# synth-zodiac-aquarius-vco.net
KiCad netlist of a schematic drawn in EAGLE
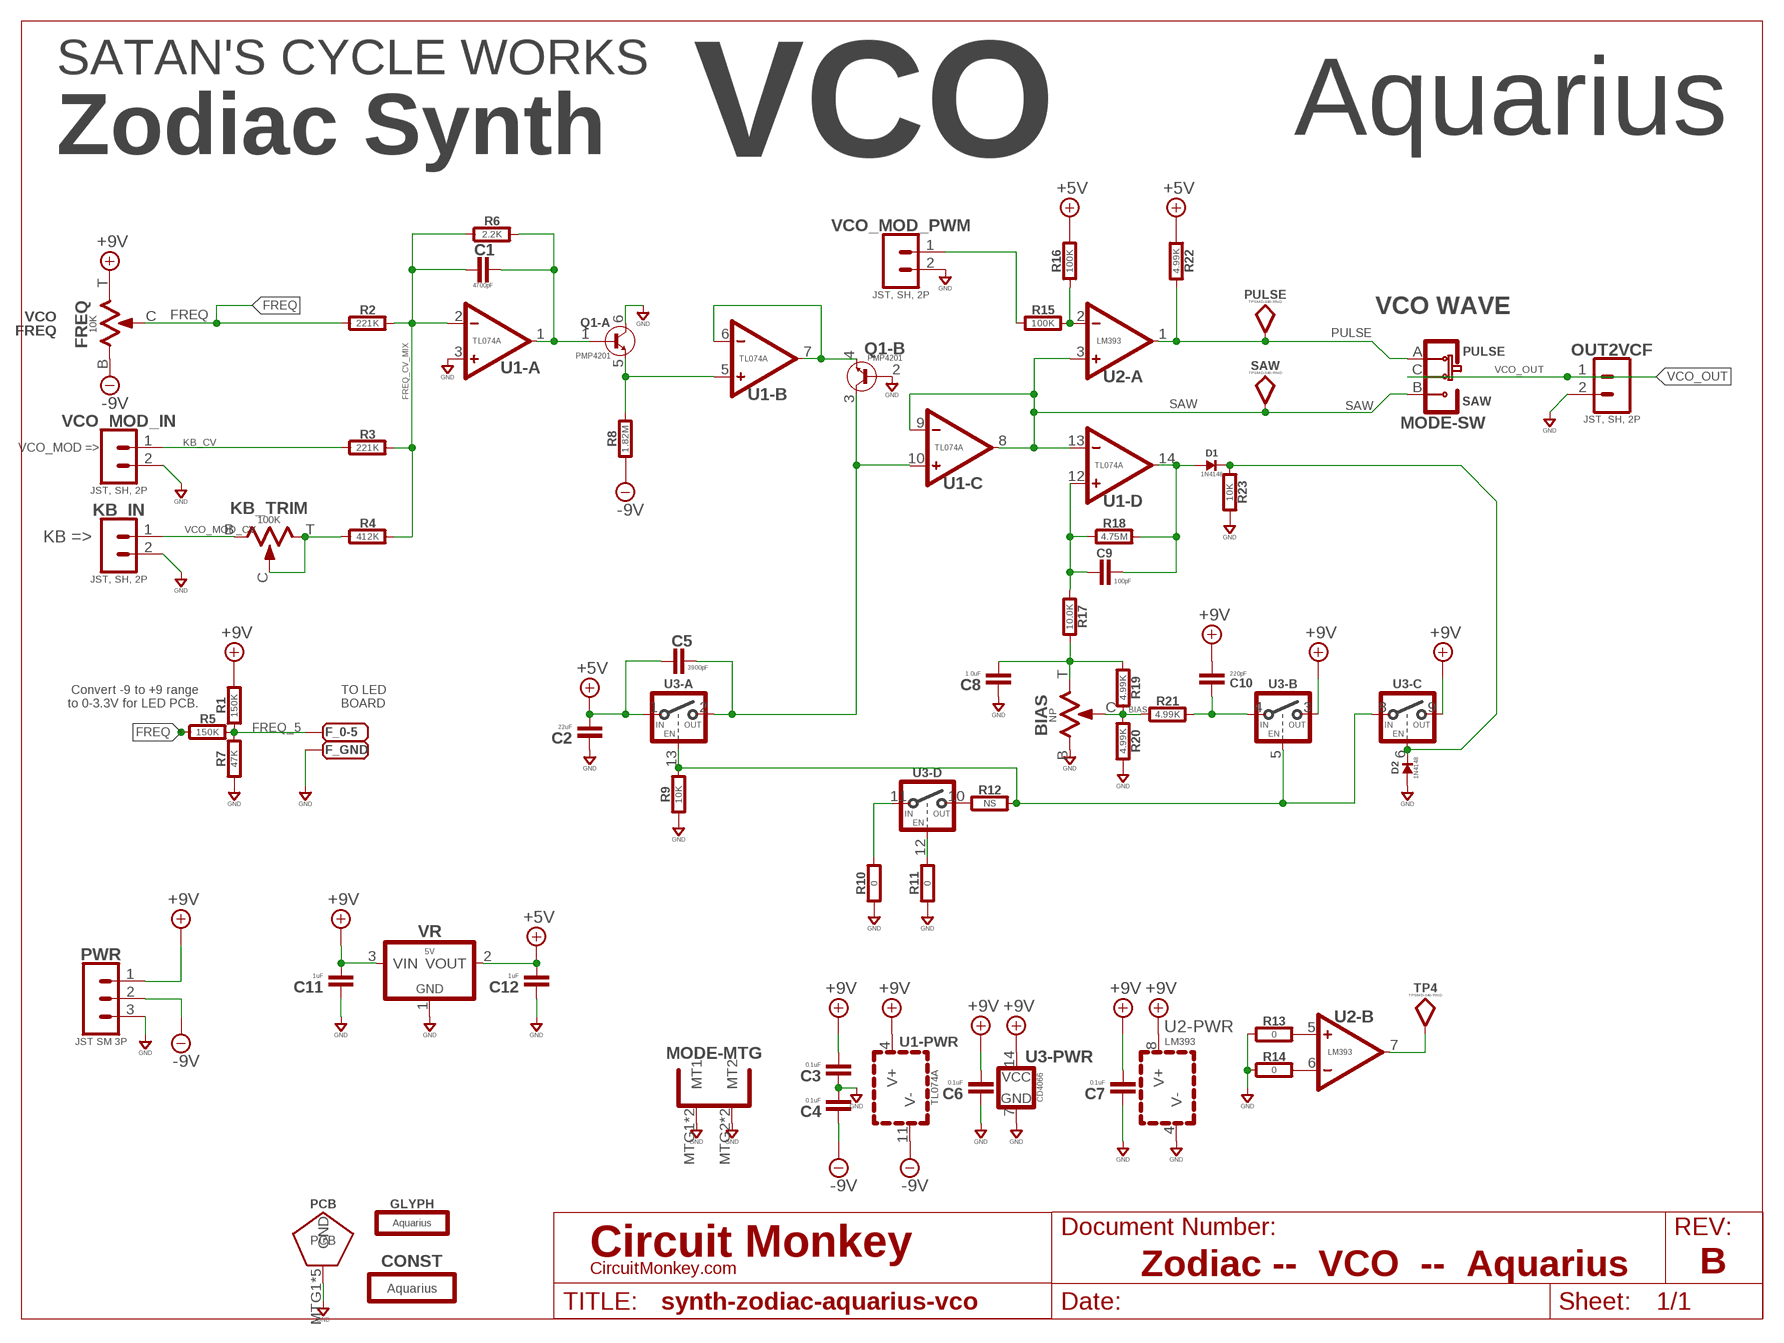
[diagram p0: schematic, sheet 1]

(export (version "E")
  (design (tool "Eeschema 10.0.6"))
  (components
    (comp (ref "BIAS")
      (value "NP")
      (footprint "eagle-import:TRIM_BOURNS_TC33X")
      (fields (field (name "MFR") "Bourns") (field (name "MPN") "TC33X"))
      (libsource (lib "eagle-import") (part "TRIMPOTTC33X"))
    )
    (comp (ref "C1")
      (value "4700pF")
      (footprint "eagle-import:0603-CAP")
      (libsource (lib "eagle-import") (part "CAPACITOR0603"))
    )
    (comp (ref "C2")
      (value "22uF")
      (footprint "eagle-import:0603-CAP")
      (libsource (lib "eagle-import") (part "CAPACITOR0603"))
    )
    (comp (ref "C3")
      (value "0.1uF")
      (footprint "eagle-import:0603-CAP")
      (libsource (lib "eagle-import") (part "CAPACITOR0603"))
    )
    (comp (ref "C4")
      (value "0.1uF")
      (footprint "eagle-import:0603-CAP")
      (libsource (lib "eagle-import") (part "CAPACITOR0603"))
    )
    (comp (ref "C5")
      (value "3900pF")
      (footprint "eagle-import:0603-CAP")
      (libsource (lib "eagle-import") (part "CAPACITOR0603"))
    )
    (comp (ref "C6")
      (value "0.1uF")
      (footprint "eagle-import:0603-CAP")
      (libsource (lib "eagle-import") (part "CAPACITOR0603"))
    )
    (comp (ref "C7")
      (value "0.1uF")
      (footprint "eagle-import:0603-CAP")
      (libsource (lib "eagle-import") (part "CAPACITOR0603"))
    )
    (comp (ref "C8")
      (value "1.0uF")
      (footprint "eagle-import:0603-CAP")
      (libsource (lib "eagle-import") (part "CAPACITOR0603"))
    )
    (comp (ref "C9")
      (value "100pF")
      (footprint "eagle-import:0603-CAP")
      (libsource (lib "eagle-import") (part "CAPACITOR0603"))
    )
    (comp (ref "C10")
      (value "220pF")
      (footprint "eagle-import:0603-CAP")
      (libsource (lib "eagle-import") (part "CAPACITOR0603"))
    )
    (comp (ref "C11")
      (value "1uF")
      (footprint "eagle-import:0603-CAP")
      (libsource (lib "eagle-import") (part "CAPACITOR0603"))
    )
    (comp (ref "C12")
      (value "1uF")
      (footprint "eagle-import:0603-CAP")
      (libsource (lib "eagle-import") (part "CAPACITOR0603"))
    )
    (comp (ref "CONST")
      (value "Aquarius")
      (footprint "eagle-import:AQUARIUS-CONST")
      (libsource (lib "eagle-import") (part "CONSTELLATION-AQUARIUS"))
    )
    (comp (ref "D1")
      (value "1N4148")
      (footprint "eagle-import:SOD-123")
      (fields (field (name "MPN") "1N4148W"))
      (libsource (lib "eagle-import") (part "DIODE-1N4148"))
    )
    (comp (ref "D2")
      (value "1N4148")
      (footprint "eagle-import:SOD-123")
      (fields (field (name "MPN") "1N4148W"))
      (libsource (lib "eagle-import") (part "DIODE-1N4148"))
    )
    (comp (ref "FREQ")
      (value "10K")
      (footprint "eagle-import:POT-RV9110")
      (fields (field (name "MFR") "Tayda") (field (name "MPN") "RV9110NO-OS15A00"))
      (libsource (lib "eagle-import") (part "TRIMPOT9MM_PCB_SHAFT"))
    )
    (comp (ref "F_0-5")
      (value "PADSMD-070X070")
      (footprint "eagle-import:SMD-070MIL")
      (libsource (lib "eagle-import") (part "PADSMD-070X070"))
    )
    (comp (ref "F_GND")
      (value "PADSMD-070X070")
      (footprint "eagle-import:SMD-070MIL")
      (libsource (lib "eagle-import") (part "PADSMD-070X070"))
    )
    (comp (ref "GLYPH")
      (value "Aquarius")
      (footprint "eagle-import:AQUARIUS-GLYPH")
      (libsource (lib "eagle-import") (part "GLYPH-AQUARIUS"))
    )
    (comp (ref "KB_IN")
      (value "JST, SH, 2P")
      (footprint "eagle-import:BM02B-SRSS-TB")
      (fields (field (name "MFR") "JST") (field (name "MPN") "BMB02B-SRSS-TB"))
      (libsource (lib "eagle-import") (part "02P-SM-VT-SMT"))
    )
    (comp (ref "KB_TRIM")
      (value "100K")
      (footprint "eagle-import:TRIM_BOURNS_TC33X")
      (fields (field (name "MFR") "Bourns") (field (name "MPN") "TC33X"))
      (libsource (lib "eagle-import") (part "TRIMPOTTC33X"))
    )
    (comp (ref "MODE")
      (value "SLIDE-SPDT-MNTSS-12-F45-TH-PCB-2")
      (footprint "eagle-import:SS-12-F45-PNL-SMT-2")
      (fields (field (name "MFR") "Tayda") (field (name "MPN") "A-659/A-5111/A-5104"))
      (libsource (lib "eagle-import") (part "SLIDE-SPDT-MNTSS-12-F45-TH-PCB-2"))
    )
    (comp (ref "OUT2VCF")
      (value "JST, SH, 2P")
      (footprint "eagle-import:BM02B-SRSS-TB")
      (fields (field (name "MFR") "JST") (field (name "MPN") "BMB02B-SRSS-TB"))
      (libsource (lib "eagle-import") (part "02P-SM-VT-SMT"))
    )
    (comp (ref "PCB")
      (value "PCB FAB")
      (footprint "eagle-import:PENTAGON-40MM-RAD")
      (libsource (lib "eagle-import") (part "PENTAGON-40R"))
    )
    (comp (ref "PULSE")
      (value "TPSMD-040-RND")
      (footprint "eagle-import:SMD-040MIL-RND")
      (libsource (lib "eagle-import") (part "TPSMD-040-RND"))
    )
    (comp (ref "PWR")
      (value "JST SM 3P")
      (footprint "eagle-import:BM03B-SRSS-TB")
      (fields (field (name "MFR") "JST") (field (name "MPN") "BM03B-SRSS-TB"))
      (libsource (lib "eagle-import") (part "03P-SM-VT-SMT"))
    )
    (comp (ref "Q1")
      (value "PMP4201")
      (footprint "eagle-import:SOT666")
      (fields (field (name "MFR") "NXP") (field (name "MPN") "PMP4201V"))
      (libsource (lib "eagle-import") (part "NPN-DUALPMP4201"))
    )
    (comp (ref "R1")
      (value "150K")
      (footprint "eagle-import:0603-RES")
      (libsource (lib "eagle-import") (part "RESISTOR0603"))
    )
    (comp (ref "R2")
      (value "221K")
      (footprint "eagle-import:0603-RES")
      (libsource (lib "eagle-import") (part "RESISTOR0603"))
    )
    (comp (ref "R3")
      (value "221K")
      (footprint "eagle-import:0603-RES")
      (libsource (lib "eagle-import") (part "RESISTOR0603"))
    )
    (comp (ref "R4")
      (value "412K")
      (footprint "eagle-import:0603-RES")
      (libsource (lib "eagle-import") (part "RESISTOR0603"))
    )
    (comp (ref "R5")
      (value "150K")
      (footprint "eagle-import:0603-RES")
      (libsource (lib "eagle-import") (part "RESISTOR0603"))
    )
    (comp (ref "R6")
      (value "2.2K")
      (footprint "eagle-import:0603-RES")
      (libsource (lib "eagle-import") (part "RESISTOR0603"))
    )
    (comp (ref "R7")
      (value "47K")
      (footprint "eagle-import:0603-RES")
      (libsource (lib "eagle-import") (part "RESISTOR0603"))
    )
    (comp (ref "R8")
      (value "1.82M")
      (footprint "eagle-import:0603-RES")
      (libsource (lib "eagle-import") (part "RESISTOR0603"))
    )
    (comp (ref "R9")
      (value "10K")
      (footprint "eagle-import:0603-RES")
      (libsource (lib "eagle-import") (part "RESISTOR0603"))
    )
    (comp (ref "R10")
      (value "0")
      (footprint "eagle-import:0603-RES")
      (libsource (lib "eagle-import") (part "RESISTOR0603"))
    )
    (comp (ref "R11")
      (value "0")
      (footprint "eagle-import:0603-RES")
      (libsource (lib "eagle-import") (part "RESISTOR0603"))
    )
    (comp (ref "R12")
      (value "NS")
      (footprint "eagle-import:0603-RES")
      (libsource (lib "eagle-import") (part "RESISTOR0603"))
    )
    (comp (ref "R13")
      (value "0")
      (footprint "eagle-import:0603-RES")
      (libsource (lib "eagle-import") (part "RESISTOR0603"))
    )
    (comp (ref "R14")
      (value "0")
      (footprint "eagle-import:0603-RES")
      (libsource (lib "eagle-import") (part "RESISTOR0603"))
    )
    (comp (ref "R15")
      (value "100K")
      (footprint "eagle-import:0603-RES")
      (libsource (lib "eagle-import") (part "RESISTOR0603"))
    )
    (comp (ref "R16")
      (value "100K")
      (footprint "eagle-import:0603-RES")
      (libsource (lib "eagle-import") (part "RESISTOR0603"))
    )
    (comp (ref "R17")
      (value "10.0K")
      (footprint "eagle-import:0603-RES")
      (libsource (lib "eagle-import") (part "RESISTOR0603"))
    )
    (comp (ref "R18")
      (value "4.75M")
      (footprint "eagle-import:0603-RES")
      (libsource (lib "eagle-import") (part "RESISTOR0603"))
    )
    (comp (ref "R19")
      (value "4.99K")
      (footprint "eagle-import:0603-RES")
      (libsource (lib "eagle-import") (part "RESISTOR0603"))
    )
    (comp (ref "R20")
      (value "4.99K")
      (footprint "eagle-import:0603-RES")
      (libsource (lib "eagle-import") (part "RESISTOR0603"))
    )
    (comp (ref "R21")
      (value "4.99K")
      (footprint "eagle-import:0603-RES")
      (libsource (lib "eagle-import") (part "RESISTOR0603"))
    )
    (comp (ref "R22")
      (value "4.99K")
      (footprint "eagle-import:0603-RES")
      (libsource (lib "eagle-import") (part "RESISTOR0603"))
    )
    (comp (ref "R23")
      (value "10K")
      (footprint "eagle-import:0603-RES")
      (libsource (lib "eagle-import") (part "RESISTOR0603"))
    )
    (comp (ref "SAW")
      (value "TPSMD-040-RND")
      (footprint "eagle-import:SMD-040MIL-RND")
      (libsource (lib "eagle-import") (part "TPSMD-040-RND"))
    )
    (comp (ref "TP4")
      (value "TPSMD-040-RND")
      (footprint "eagle-import:SMD-040MIL-RND")
      (libsource (lib "eagle-import") (part "TPSMD-040-RND"))
    )
    (comp (ref "U1")
      (value "TL074A")
      (footprint "eagle-import:SOP14")
      (fields (field (name "MFR") "ST") (field (name "MPN") "TL074ACDT"))
      (libsource (lib "eagle-import") (part "QUADTL074A-SOIC"))
    )
    (comp (ref "U2")
      (value "LM393")
      (footprint "eagle-import:SOP08")
      (fields (field (name "MFR") "ST") (field (name "MPN") "LM393ED"))
      (libsource (lib "eagle-import") (part "DUAL-LM393ED"))
    )
    (comp (ref "U3")
      (value "CD4066")
      (footprint "eagle-import:SOP14")
      (fields (field (name "MFR") "TI") (field (name "MPN") "CD4066BM"))
      (libsource (lib "eagle-import") (part "CD4066SO14"))
    )
    (comp (ref "VCO_MOD_IN")
      (value "JST, SH, 2P")
      (footprint "eagle-import:BM02B-SRSS-TB")
      (fields (field (name "MFR") "JST") (field (name "MPN") "BMB02B-SRSS-TB"))
      (libsource (lib "eagle-import") (part "02P-SM-VT-SMT"))
    )
    (comp (ref "VCO_MOD_PWM")
      (value "JST, SH, 2P")
      (footprint "eagle-import:BM02B-SRSS-TB")
      (fields (field (name "MFR") "JST") (field (name "MPN") "BMB02B-SRSS-TB"))
      (libsource (lib "eagle-import") (part "02P-SM-VT-SMT"))
    )
    (comp (ref "VR")
      (value "5V")
      (footprint "eagle-import:SOT-23")
      (fields (field (name "MFR") "Diodes, Inc.") (field (name "MPN") "AP7387-50SA"))
      (libsource (lib "eagle-import") (part "LDO-3P--5V-SOT23"))
    )
  )
  (nets
    (net (code "1") (name "+5V") (class "Default")
      (node (ref "C12") (pin "2") (pinfunction "2_2") (pintype "passive"))
      (node (ref "C2") (pin "2") (pinfunction "2_2") (pintype "passive"))
      (node (ref "C5") (pin "1") (pinfunction "1_1") (pintype "passive"))
      (node (ref "R16") (pin "2") (pinfunction "2_2") (pintype "passive"))
      (node (ref "R22") (pin "1") (pinfunction "1_1") (pintype "passive"))
      (node (ref "U3") (pin "1") (pinfunction "IN_1") (pintype "bidirectional"))
      (node (ref "VR") (pin "2") (pinfunction "VOUT_2") (pintype "power_in"))
    )
    (net (code "2") (name "+9V") (class "Default")
      (node (ref "C10") (pin "2") (pinfunction "2_2") (pintype "passive"))
      (node (ref "C11") (pin "2") (pinfunction "2_2") (pintype "passive"))
      (node (ref "C3") (pin "2") (pinfunction "2_2") (pintype "passive"))
      (node (ref "C6") (pin "2") (pinfunction "2_2") (pintype "passive"))
      (node (ref "C7") (pin "2") (pinfunction "2_2") (pintype "passive"))
      (node (ref "FREQ") (pin "T") (pinfunction "3_T") (pintype "passive"))
      (node (ref "PWR") (pin "1") (pinfunction "1_1") (pintype "passive"))
      (node (ref "R1") (pin "2") (pinfunction "2_2") (pintype "passive"))
      (node (ref "U1") (pin "4") (pinfunction "V+_4") (pintype "power_in"))
      (node (ref "U2") (pin "8") (pinfunction "V+_8") (pintype "power_in"))
      (node (ref "U3") (pin "14") (pinfunction "VCC_14") (pintype "power_in"))
      (node (ref "U3") (pin "3") (pinfunction "OUT_3") (pintype "bidirectional"))
      (node (ref "U3") (pin "9") (pinfunction "OUT_9") (pintype "bidirectional"))
      (node (ref "VR") (pin "3") (pinfunction "VIN_3") (pintype "power_in"))
    )
    (net (code "3") (name "-9V") (class "Default")
      (node (ref "C4") (pin "1") (pinfunction "1_1") (pintype "passive"))
      (node (ref "FREQ") (pin "B") (pinfunction "1_B") (pintype "passive"))
      (node (ref "PWR") (pin "2") (pinfunction "2_2") (pintype "passive"))
      (node (ref "R8") (pin "1") (pinfunction "1_1") (pintype "passive"))
      (node (ref "U1") (pin "11") (pinfunction "V-_11") (pintype "power_in"))
    )
    (net (code "4") (name "/BIAS") (class "Default")
      (node (ref "BIAS") (pin "C") (pinfunction "2_C") (pintype "passive"))
      (node (ref "R19") (pin "2") (pinfunction "2_2") (pintype "passive"))
      (node (ref "R20") (pin "1") (pinfunction "1_1") (pintype "passive"))
      (node (ref "R21") (pin "1") (pinfunction "1_1") (pintype "passive"))
    )
    (net (code "5") (name "/FREQ_5") (class "Default")
      (node (ref "F_0-5") (pin "1") (pinfunction "PAD_1") (pintype "bidirectional"))
      (node (ref "R1") (pin "1") (pinfunction "1_1") (pintype "passive"))
      (node (ref "R5") (pin "2") (pinfunction "2_2") (pintype "passive"))
      (node (ref "R7") (pin "2") (pinfunction "2_2") (pintype "passive"))
    )
    (net (code "6") (name "/FREQ_CV_MIX") (class "Default")
      (node (ref "C1") (pin "1") (pinfunction "1_1") (pintype "passive"))
      (node (ref "R2") (pin "2") (pinfunction "2_2") (pintype "passive"))
      (node (ref "R3") (pin "2") (pinfunction "2_2") (pintype "passive"))
      (node (ref "R4") (pin "2") (pinfunction "2_2") (pintype "passive"))
      (node (ref "R6") (pin "1") (pinfunction "1_1") (pintype "passive"))
      (node (ref "U1") (pin "2") (pinfunction "-_2") (pintype "input"))
    )
    (net (code "7") (name "/KB_CV") (class "Default")
      (node (ref "KB_IN") (pin "1") (pinfunction "1_1") (pintype "passive"))
      (node (ref "KB_TRIM") (pin "B") (pinfunction "1_B") (pintype "passive"))
    )
    (net (code "8") (name "/PULSE") (class "Default")
      (node (ref "MODE") (pin "A") (pinfunction "A_A") (pintype "bidirectional"))
      (node (ref "PULSE") (pin "TP") (pinfunction "P$1_TP") (pintype "bidirectional"))
      (node (ref "R22") (pin "2") (pinfunction "2_2") (pintype "passive"))
      (node (ref "U2") (pin "1") (pinfunction "OUT_1") (pintype "output"))
    )
    (net (code "9") (name "/SAW") (class "Default")
      (node (ref "MODE") (pin "B") (pinfunction "B_B") (pintype "bidirectional"))
      (node (ref "SAW") (pin "TP") (pinfunction "P$1_TP") (pintype "bidirectional"))
      (node (ref "U1") (pin "13") (pinfunction "-_13") (pintype "input"))
      (node (ref "U1") (pin "8") (pinfunction "OUT_8") (pintype "output"))
      (node (ref "U1") (pin "9") (pinfunction "-_9") (pintype "input"))
      (node (ref "U2") (pin "3") (pinfunction "+_3") (pintype "input"))
    )
    (net (code "10") (name "/VCO_MOD_CV") (class "Default")
      (node (ref "R3") (pin "1") (pinfunction "1_1") (pintype "passive"))
      (node (ref "VCO_MOD_IN") (pin "1") (pinfunction "1_1") (pintype "passive"))
    )
    (net (code "11") (name "FREQ") (class "Default")
      (node (ref "FREQ") (pin "C") (pinfunction "2_C") (pintype "passive"))
      (node (ref "R2") (pin "1") (pinfunction "1_1") (pintype "passive"))
      (node (ref "R5") (pin "1") (pinfunction "1_1") (pintype "passive"))
    )
    (net (code "12") (name "GND") (class "Default")
      (node (ref "BIAS") (pin "B") (pinfunction "1_B") (pintype "passive"))
      (node (ref "C11") (pin "1") (pinfunction "1_1") (pintype "passive"))
      (node (ref "C12") (pin "1") (pinfunction "1_1") (pintype "passive"))
      (node (ref "C2") (pin "1") (pinfunction "1_1") (pintype "passive"))
      (node (ref "C3") (pin "1") (pinfunction "1_1") (pintype "passive"))
      (node (ref "C4") (pin "2") (pinfunction "2_2") (pintype "passive"))
      (node (ref "C6") (pin "1") (pinfunction "1_1") (pintype "passive"))
      (node (ref "C7") (pin "1") (pinfunction "1_1") (pintype "passive"))
      (node (ref "C8") (pin "1") (pinfunction "1_1") (pintype "passive"))
      (node (ref "D2") (pin "A") (pinfunction "A_A") (pintype "passive"))
      (node (ref "F_GND") (pin "1") (pinfunction "PAD_1") (pintype "bidirectional"))
      (node (ref "KB_IN") (pin "2") (pinfunction "2_2") (pintype "passive"))
      (node (ref "MODE") (pin "MTG1") (pinfunction "MT1_MTG1") (pintype "bidirectional"))
      (node (ref "MODE") (pin "MTG2") (pinfunction "MT2_MTG2") (pintype "bidirectional"))
      (node (ref "MODE") (pin "MTG3") (pinfunction "MT1_MTG3") (pintype "bidirectional"))
      (node (ref "MODE") (pin "MTG4") (pinfunction "MT2_MTG4") (pintype "bidirectional"))
      (node (ref "OUT2VCF") (pin "2") (pinfunction "2_2") (pintype "passive"))
      (node (ref "PCB") (pin "MTG1") (pinfunction "GND_MTG1") (pintype "bidirectional"))
      (node (ref "PCB") (pin "MTG2") (pinfunction "GND_MTG2") (pintype "bidirectional"))
      (node (ref "PCB") (pin "MTG3") (pinfunction "GND_MTG3") (pintype "bidirectional"))
      (node (ref "PCB") (pin "MTG4") (pinfunction "GND_MTG4") (pintype "bidirectional"))
      (node (ref "PCB") (pin "MTG5") (pinfunction "GND_MTG5") (pintype "bidirectional"))
      (node (ref "PWR") (pin "3") (pinfunction "3_3") (pintype "passive"))
      (node (ref "Q1") (pin "2") (pinfunction "BASE_2") (pintype "bidirectional"))
      (node (ref "Q1") (pin "6") (pinfunction "COLLECTOR_6") (pintype "bidirectional"))
      (node (ref "R10") (pin "1") (pinfunction "1_1") (pintype "passive"))
      (node (ref "R11") (pin "1") (pinfunction "1_1") (pintype "passive"))
      (node (ref "R13") (pin "1") (pinfunction "1_1") (pintype "passive"))
      (node (ref "R14") (pin "1") (pinfunction "1_1") (pintype "passive"))
      (node (ref "R20") (pin "2") (pinfunction "2_2") (pintype "passive"))
      (node (ref "R23") (pin "2") (pinfunction "2_2") (pintype "passive"))
      (node (ref "R7") (pin "1") (pinfunction "1_1") (pintype "passive"))
      (node (ref "R9") (pin "1") (pinfunction "1_1") (pintype "passive"))
      (node (ref "U1") (pin "3") (pinfunction "+_3") (pintype "input"))
      (node (ref "U2") (pin "4") (pinfunction "V-_4") (pintype "power_in"))
      (node (ref "U3") (pin "7") (pinfunction "GND_7") (pintype "power_in"))
      (node (ref "VCO_MOD_IN") (pin "2") (pinfunction "2_2") (pintype "passive"))
      (node (ref "VCO_MOD_PWM") (pin "2") (pinfunction "2_2") (pintype "passive"))
      (node (ref "VR") (pin "1") (pinfunction "GND_1") (pintype "power_in"))
    )
    (net (code "13") (name "Net-(BIAS-3)") (class "Default")
      (node (ref "BIAS") (pin "T") (pinfunction "3_T") (pintype "passive"))
      (node (ref "C8") (pin "2") (pinfunction "2_2") (pintype "passive"))
      (node (ref "R17") (pin "2") (pinfunction "2_2") (pintype "passive"))
      (node (ref "R19") (pin "1") (pinfunction "1_1") (pintype "passive"))
    )
    (net (code "14") (name "Net-(KB_TRIM-2)") (class "Default")
      (node (ref "KB_TRIM") (pin "C") (pinfunction "2_C") (pintype "passive"))
      (node (ref "KB_TRIM") (pin "T") (pinfunction "3_T") (pintype "passive"))
      (node (ref "R4") (pin "1") (pinfunction "1_1") (pintype "passive"))
    )
    (net (code "15") (name "Net-(Q1A-BASE)") (class "Default")
      (node (ref "C1") (pin "2") (pinfunction "2_2") (pintype "passive"))
      (node (ref "Q1") (pin "1") (pinfunction "BASE_1") (pintype "bidirectional"))
      (node (ref "R6") (pin "2") (pinfunction "2_2") (pintype "passive"))
      (node (ref "U1") (pin "1") (pinfunction "OUT_1") (pintype "output"))
    )
    (net (code "16") (name "Net-(Q1A-EMITTER)") (class "Default")
      (node (ref "Q1") (pin "5") (pinfunction "EMITTER_5") (pintype "bidirectional"))
      (node (ref "R8") (pin "2") (pinfunction "2_2") (pintype "passive"))
      (node (ref "U1") (pin "5") (pinfunction "+_5") (pintype "input"))
    )
    (net (code "17") (name "Net-(Q1B-COLLECTOR)") (class "Default")
      (node (ref "C5") (pin "2") (pinfunction "2_2") (pintype "passive"))
      (node (ref "Q1") (pin "3") (pinfunction "COLLECTOR_3") (pintype "bidirectional"))
      (node (ref "U1") (pin "10") (pinfunction "+_10") (pintype "input"))
      (node (ref "U3") (pin "2") (pinfunction "OUT_2") (pintype "bidirectional"))
    )
    (net (code "18") (name "Net-(Q1B-EMITTER)") (class "Default")
      (node (ref "Q1") (pin "4") (pinfunction "EMITTER_4") (pintype "bidirectional"))
      (node (ref "U1") (pin "6") (pinfunction "-_6") (pintype "input"))
      (node (ref "U1") (pin "7") (pinfunction "OUT_7") (pintype "output"))
    )
    (net (code "19") (name "Net-(R15-Pad1)") (class "Default")
      (node (ref "R15") (pin "1") (pinfunction "1_1") (pintype "passive"))
      (node (ref "VCO_MOD_PWM") (pin "1") (pinfunction "1_1") (pintype "passive"))
    )
    (net (code "20") (name "Net-(TP4-P$1)") (class "Default")
      (node (ref "TP4") (pin "TP") (pinfunction "P$1_TP") (pintype "bidirectional"))
      (node (ref "U2") (pin "7") (pinfunction "OUT_7") (pintype "output"))
    )
    (net (code "21") (name "Net-(U1D-+)") (class "Default")
      (node (ref "C9") (pin "1") (pinfunction "1_1") (pintype "passive"))
      (node (ref "R17") (pin "1") (pinfunction "1_1") (pintype "passive"))
      (node (ref "R18") (pin "1") (pinfunction "1_1") (pintype "passive"))
      (node (ref "U1") (pin "12") (pinfunction "+_12") (pintype "input"))
    )
    (net (code "22") (name "Net-(U1D-OUT)") (class "Default")
      (node (ref "C9") (pin "2") (pinfunction "2_2") (pintype "passive"))
      (node (ref "D1") (pin "A") (pinfunction "A_A") (pintype "passive"))
      (node (ref "R18") (pin "2") (pinfunction "2_2") (pintype "passive"))
      (node (ref "U1") (pin "14") (pinfunction "OUT_14") (pintype "output"))
    )
    (net (code "23") (name "Net-(U2A--)") (class "Default")
      (node (ref "R15") (pin "2") (pinfunction "2_2") (pintype "passive"))
      (node (ref "R16") (pin "1") (pinfunction "1_1") (pintype "passive"))
      (node (ref "U2") (pin "2") (pinfunction "-_2") (pintype "input"))
    )
    (net (code "24") (name "Net-(U2B-+)") (class "Default")
      (node (ref "R13") (pin "2") (pinfunction "2_2") (pintype "passive"))
      (node (ref "U2") (pin "5") (pinfunction "+_5") (pintype "input"))
    )
    (net (code "25") (name "Net-(U2B--)") (class "Default")
      (node (ref "R14") (pin "2") (pinfunction "2_2") (pintype "passive"))
      (node (ref "U2") (pin "6") (pinfunction "-_6") (pintype "input"))
    )
    (net (code "26") (name "Net-(U3A-EN)") (class "Default")
      (node (ref "R12") (pin "2") (pinfunction "2_2") (pintype "passive"))
      (node (ref "R9") (pin "2") (pinfunction "2_2") (pintype "passive"))
      (node (ref "U3") (pin "13") (pinfunction "EN_13") (pintype "bidirectional"))
      (node (ref "U3") (pin "5") (pinfunction "EN_5") (pintype "bidirectional"))
      (node (ref "U3") (pin "8") (pinfunction "IN_8") (pintype "bidirectional"))
    )
    (net (code "27") (name "Net-(U3B-IN)") (class "Default")
      (node (ref "C10") (pin "1") (pinfunction "1_1") (pintype "passive"))
      (node (ref "R21") (pin "2") (pinfunction "2_2") (pintype "passive"))
      (node (ref "U3") (pin "4") (pinfunction "IN_4") (pintype "bidirectional"))
    )
    (net (code "28") (name "Net-(U3C-EN)") (class "Default")
      (node (ref "D1") (pin "K") (pinfunction "K_K") (pintype "passive"))
      (node (ref "D2") (pin "K") (pinfunction "K_K") (pintype "passive"))
      (node (ref "R23") (pin "1") (pinfunction "1_1") (pintype "passive"))
      (node (ref "U3") (pin "6") (pinfunction "EN_6") (pintype "bidirectional"))
    )
    (net (code "29") (name "Net-(U3D-EN)") (class "Default")
      (node (ref "R11") (pin "2") (pinfunction "2_2") (pintype "passive"))
      (node (ref "U3") (pin "12") (pinfunction "EN_12") (pintype "bidirectional"))
    )
    (net (code "30") (name "Net-(U3D-IN)") (class "Default")
      (node (ref "R10") (pin "2") (pinfunction "2_2") (pintype "passive"))
      (node (ref "U3") (pin "11") (pinfunction "IN_11") (pintype "bidirectional"))
    )
    (net (code "31") (name "Net-(U3D-OUT)") (class "Default")
      (node (ref "R12") (pin "1") (pinfunction "1_1") (pintype "passive"))
      (node (ref "U3") (pin "10") (pinfunction "OUT_10") (pintype "bidirectional"))
    )
    (net (code "32") (name "VCO_OUT") (class "Default")
      (node (ref "MODE") (pin "C") (pinfunction "C_C") (pintype "bidirectional"))
      (node (ref "OUT2VCF") (pin "1") (pinfunction "1_1") (pintype "passive"))
    )
  )
)
